# dirtypunk.net
KiCad netlist of a schematic drawn in EAGLE
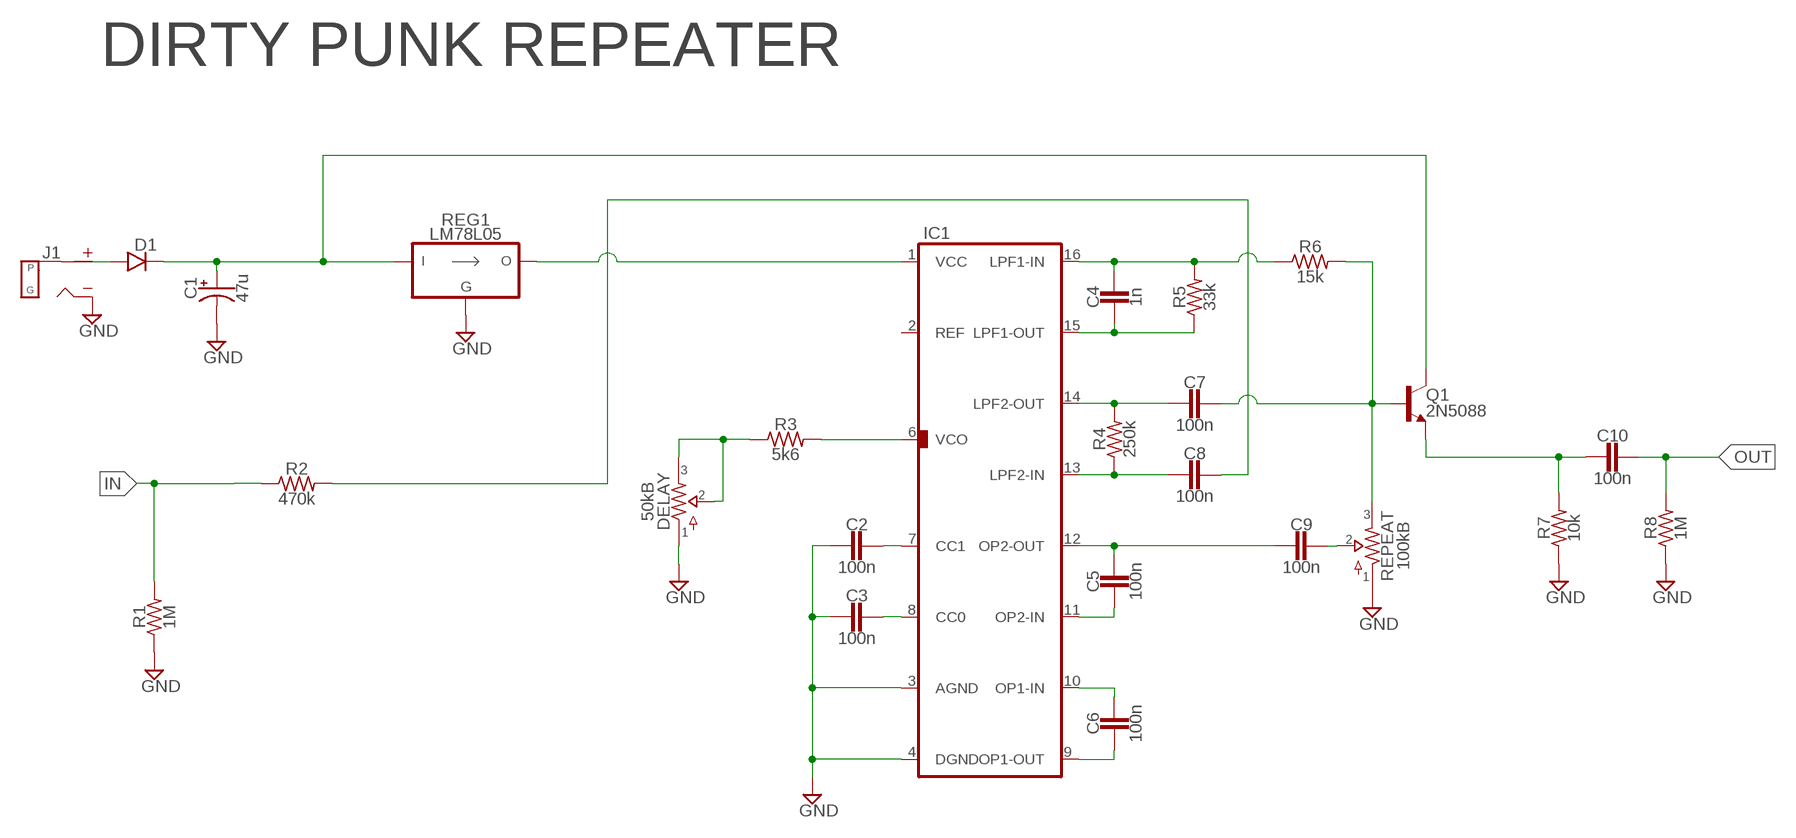
[diagram p0: schematic, sheet 1]

(export (version "E")
  (design (tool "Eeschema 10.0.6"))
  (components
    (comp (ref "C1")
      (value "47u")
      (footprint "eagle-import:050_020_1")
      (libsource (lib "eagle-import") (part "0501"))
    )
    (comp (ref "C2")
      (value "100n")
      (footprint "eagle-import:050X030_025_2")
      (libsource (lib "eagle-import") (part "CER/FILM2"))
    )
    (comp (ref "C3")
      (value "100n")
      (footprint "eagle-import:050X030_025_2")
      (libsource (lib "eagle-import") (part "CER/FILM2"))
    )
    (comp (ref "C4")
      (value "1n")
      (footprint "eagle-import:050X030_025_2")
      (libsource (lib "eagle-import") (part "CER/FILM2"))
    )
    (comp (ref "C5")
      (value "100n")
      (footprint "eagle-import:050X030_025_2")
      (libsource (lib "eagle-import") (part "CER/FILM2"))
    )
    (comp (ref "C6")
      (value "100n")
      (footprint "eagle-import:050X030_025_2")
      (libsource (lib "eagle-import") (part "CER/FILM2"))
    )
    (comp (ref "C7")
      (value "100n")
      (footprint "eagle-import:050X030_025_2")
      (libsource (lib "eagle-import") (part "CER/FILM2"))
    )
    (comp (ref "C8")
      (value "100n")
      (footprint "eagle-import:050X030_025_2")
      (libsource (lib "eagle-import") (part "CER/FILM2"))
    )
    (comp (ref "C9")
      (value "100n")
      (footprint "eagle-import:050X030_025_2")
      (libsource (lib "eagle-import") (part "CER/FILM2"))
    )
    (comp (ref "C10")
      (value "100n")
      (footprint "eagle-import:050X030_025_2")
      (libsource (lib "eagle-import") (part "CER/FILM2"))
    )
    (comp (ref "D1")
      (value "DO41.3")
      (footprint "eagle-import:DO41-3")
      (libsource (lib "eagle-import") (part "DO41.3"))
    )
    (comp (ref "DELAY")
      (value "50kB")
      (footprint "eagle-import:PADS_SMALL")
      (libsource (lib "eagle-import") (part "POTSSMALL_PADS"))
    )
    (comp (ref "IC1")
      (value "PT2399TH")
      (footprint "eagle-import:DIL16")
      (libsource (lib "eagle-import") (part "PT2399TH"))
    )
    (comp (ref "J1")
      (value "DC_MONO")
      (footprint "eagle-import:DC")
      (libsource (lib "eagle-import") (part "DC_MONO"))
    )
    (comp (ref "Q1")
      (value "2N5088")
      (footprint "eagle-import:TO92-")
      (libsource (lib "eagle-import") (part "2N5088"))
    )
    (comp (ref "R1")
      (value "1M")
      (footprint "eagle-import:R0207_2V")
      (libsource (lib "eagle-import") (part "R_.2"))
    )
    (comp (ref "R2")
      (value "470k")
      (footprint "eagle-import:R0207_2V")
      (libsource (lib "eagle-import") (part "R_.2"))
    )
    (comp (ref "R3")
      (value "5k6")
      (footprint "eagle-import:R0207_2V")
      (libsource (lib "eagle-import") (part "R_.2"))
    )
    (comp (ref "R4")
      (value "250k")
      (footprint "eagle-import:R0207_2V")
      (libsource (lib "eagle-import") (part "R_.2"))
    )
    (comp (ref "R5")
      (value "33k")
      (footprint "eagle-import:R0207_2V")
      (libsource (lib "eagle-import") (part "R_.2"))
    )
    (comp (ref "R6")
      (value "15k")
      (footprint "eagle-import:R0207_2V")
      (libsource (lib "eagle-import") (part "R_.2"))
    )
    (comp (ref "R7")
      (value "10k")
      (footprint "eagle-import:R0207_2V")
      (libsource (lib "eagle-import") (part "R_.2"))
    )
    (comp (ref "R8")
      (value "1M")
      (footprint "eagle-import:R0207_2V")
      (libsource (lib "eagle-import") (part "R_.2"))
    )
    (comp (ref "REG1")
      (value "LM78L05")
      (footprint "eagle-import:TO92-")
      (libsource (lib "eagle-import") (part "LM78L05"))
    )
    (comp (ref "REPEAT")
      (value "100kB")
      (footprint "eagle-import:PADS_SMALL")
      (libsource (lib "eagle-import") (part "POTSSMALL_PADS"))
    )
  )
  (nets
    (net (code "1") (name "GND") (class "Default")
      (node (ref "C1") (pin "-") (pinfunction "-_-") (pintype "passive"))
      (node (ref "C2") (pin "2") (pinfunction "2_2") (pintype "passive"))
      (node (ref "C3") (pin "2") (pinfunction "2_2") (pintype "passive"))
      (node (ref "DELAY") (pin "1") (pinfunction "1_1") (pintype "passive"))
      (node (ref "IC1") (pin "3") (pinfunction "AGND_3") (pintype "power_in"))
      (node (ref "IC1") (pin "4") (pinfunction "DGND_4") (pintype "power_in"))
      (node (ref "J1") (pin "S") (pinfunction "SLEEVE_S") (pintype "passive"))
      (node (ref "R1") (pin "1") (pinfunction "1_1") (pintype "passive"))
      (node (ref "R7") (pin "1") (pinfunction "1_1") (pintype "passive"))
      (node (ref "R8") (pin "1") (pinfunction "1_1") (pintype "passive"))
      (node (ref "REG1") (pin "2") (pinfunction "GND_2") (pintype "passive"))
      (node (ref "REPEAT") (pin "1") (pinfunction "1_1") (pintype "passive"))
    )
    (net (code "2") (name "IN") (class "Default")
      (node (ref "R1") (pin "2") (pinfunction "2_2") (pintype "passive"))
      (node (ref "R2") (pin "1") (pinfunction "1_1") (pintype "passive"))
    )
    (net (code "3") (name "Net-(C8-Pad1)") (class "Default")
      (node (ref "C8") (pin "1") (pinfunction "1_1") (pintype "passive"))
      (node (ref "R2") (pin "2") (pinfunction "2_2") (pintype "passive"))
    )
    (net (code "4") (name "Net-(C9-Pad1)") (class "Default")
      (node (ref "C9") (pin "1") (pinfunction "1_1") (pintype "passive"))
      (node (ref "REPEAT") (pin "2") (pinfunction "2_2") (pintype "passive"))
    )
    (net (code "5") (name "Net-(DELAY-Pad2)") (class "Default")
      (node (ref "DELAY") (pin "2") (pinfunction "2_2") (pintype "passive"))
      (node (ref "DELAY") (pin "3") (pinfunction "3_3") (pintype "passive"))
      (node (ref "R3") (pin "1") (pinfunction "1_1") (pintype "passive"))
    )
    (net (code "6") (name "Net-(IC1-CC0)") (class "Default")
      (node (ref "C3") (pin "1") (pinfunction "1_1") (pintype "passive"))
      (node (ref "IC1") (pin "8") (pinfunction "CC0_8") (pintype "input"))
    )
    (net (code "7") (name "Net-(IC1-CC1)") (class "Default")
      (node (ref "C2") (pin "1") (pinfunction "1_1") (pintype "passive"))
      (node (ref "IC1") (pin "7") (pinfunction "CC1_7") (pintype "input"))
    )
    (net (code "8") (name "Net-(IC1-LPF1-IN)") (class "Default")
      (node (ref "C4") (pin "1") (pinfunction "1_1") (pintype "passive"))
      (node (ref "IC1") (pin "16") (pinfunction "LPF1-IN_16") (pintype "input"))
      (node (ref "R5") (pin "2") (pinfunction "2_2") (pintype "passive"))
      (node (ref "R6") (pin "1") (pinfunction "1_1") (pintype "passive"))
    )
    (net (code "9") (name "Net-(IC1-LPF1-OUT)") (class "Default")
      (node (ref "C4") (pin "2") (pinfunction "2_2") (pintype "passive"))
      (node (ref "IC1") (pin "15") (pinfunction "LPF1-OUT_15") (pintype "output"))
      (node (ref "R5") (pin "1") (pinfunction "1_1") (pintype "passive"))
    )
    (net (code "10") (name "Net-(IC1-LPF2-IN)") (class "Default")
      (node (ref "C8") (pin "2") (pinfunction "2_2") (pintype "passive"))
      (node (ref "IC1") (pin "13") (pinfunction "LPF2-IN_13") (pintype "input"))
      (node (ref "R4") (pin "1") (pinfunction "1_1") (pintype "passive"))
    )
    (net (code "11") (name "Net-(IC1-LPF2-OUT)") (class "Default")
      (node (ref "C7") (pin "2") (pinfunction "2_2") (pintype "passive"))
      (node (ref "IC1") (pin "14") (pinfunction "LPF2-OUT_14") (pintype "output"))
      (node (ref "R4") (pin "2") (pinfunction "2_2") (pintype "passive"))
    )
    (net (code "12") (name "Net-(IC1-OP1-IN)") (class "Default")
      (node (ref "C6") (pin "1") (pinfunction "1_1") (pintype "passive"))
      (node (ref "IC1") (pin "10") (pinfunction "OP1-IN_10") (pintype "input"))
    )
    (net (code "13") (name "Net-(IC1-OP1-OUT)") (class "Default")
      (node (ref "C6") (pin "2") (pinfunction "2_2") (pintype "passive"))
      (node (ref "IC1") (pin "9") (pinfunction "OP1-OUT_9") (pintype "output"))
    )
    (net (code "14") (name "Net-(IC1-OP2-IN)") (class "Default")
      (node (ref "C5") (pin "2") (pinfunction "2_2") (pintype "passive"))
      (node (ref "IC1") (pin "11") (pinfunction "OP2-IN_11") (pintype "input"))
    )
    (net (code "15") (name "Net-(IC1-OP2-OUT)") (class "Default")
      (node (ref "C5") (pin "1") (pinfunction "1_1") (pintype "passive"))
      (node (ref "C9") (pin "2") (pinfunction "2_2") (pintype "passive"))
      (node (ref "IC1") (pin "12") (pinfunction "OP2-OUT_12") (pintype "output"))
    )
    (net (code "16") (name "Net-(IC1-VCC)") (class "Default")
      (node (ref "IC1") (pin "1") (pinfunction "VCC_1") (pintype "power_in"))
      (node (ref "REG1") (pin "3") (pinfunction "VO_3") (pintype "passive"))
    )
    (net (code "17") (name "Net-(IC1-VCO)") (class "Default")
      (node (ref "IC1") (pin "6") (pinfunction "VCO_6") (pintype "input"))
      (node (ref "R3") (pin "2") (pinfunction "2_2") (pintype "passive"))
    )
    (net (code "18") (name "Net-(J1-TIP)") (class "Default")
      (node (ref "D1") (pin "A") (pinfunction "A_A") (pintype "passive"))
      (node (ref "J1") (pin "T") (pinfunction "TIP_T") (pintype "passive"))
    )
    (net (code "19") (name "Net-(Q1-B)") (class "Default")
      (node (ref "C7") (pin "1") (pinfunction "1_1") (pintype "passive"))
      (node (ref "Q1") (pin "2") (pinfunction "B_2") (pintype "passive"))
      (node (ref "R6") (pin "2") (pinfunction "2_2") (pintype "passive"))
      (node (ref "REPEAT") (pin "3") (pinfunction "3_3") (pintype "passive"))
    )
    (net (code "20") (name "Net-(Q1-C)") (class "Default")
      (node (ref "C1") (pin "+") (pinfunction "+_+") (pintype "passive"))
      (node (ref "D1") (pin "C") (pinfunction "C_C") (pintype "passive"))
      (node (ref "Q1") (pin "1") (pinfunction "C_1") (pintype "passive"))
      (node (ref "REG1") (pin "1") (pinfunction "VI_1") (pintype "input"))
    )
    (net (code "21") (name "Net-(Q1-E)") (class "Default")
      (node (ref "C10") (pin "2") (pinfunction "2_2") (pintype "passive"))
      (node (ref "Q1") (pin "3") (pinfunction "E_3") (pintype "passive"))
      (node (ref "R7") (pin "2") (pinfunction "2_2") (pintype "passive"))
    )
    (net (code "22") (name "OUT") (class "Default")
      (node (ref "C10") (pin "1") (pinfunction "1_1") (pintype "passive"))
      (node (ref "R8") (pin "2") (pinfunction "2_2") (pintype "passive"))
    )
    (net (code "23") (name "unconnected-(IC1-REF-Pad2)") (class "Default")
      (node (ref "IC1") (pin "2") (pinfunction "REF_2") (pintype "input"))
    )
  )
)
